# MC_amp.net
KiCad netlist of a schematic drawn in EAGLE
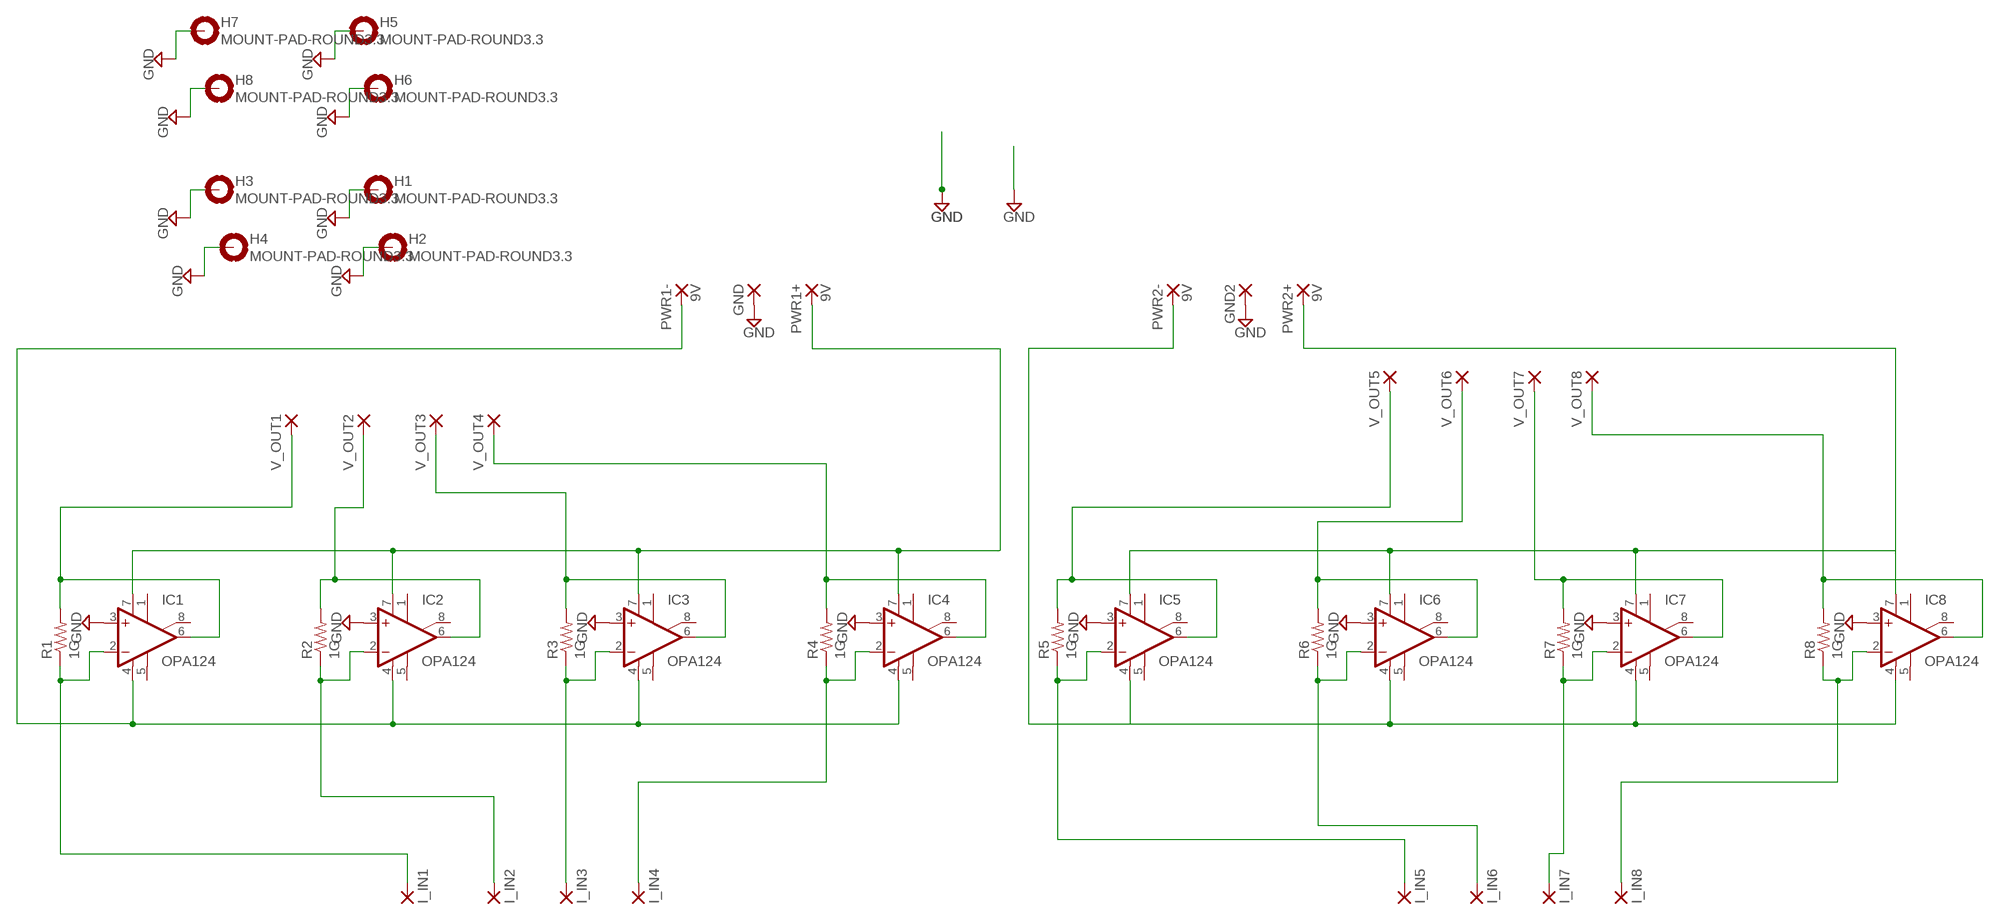
[diagram p0: schematic, sheet 1]

(export (version "E")
  (design (tool "Eeschema 10.0.6"))
  (components
    (comp (ref "GND")
      (value "1,6/0,8")
      (footprint "eagle-import:1,6_0,8")
      (libsource (lib "eagle-import") (part "1,6/0,8"))
    )
    (comp (ref "GND2")
      (value "1,6/0,8")
      (footprint "eagle-import:1,6_0,8")
      (libsource (lib "eagle-import") (part "1,6/0,8"))
    )
    (comp (ref "H1")
      (value "MOUNT-PAD-ROUND3.3")
      (footprint "eagle-import:3,3-PAD")
      (libsource (lib "eagle-import") (part "MOUNT-PAD-ROUND3.3"))
    )
    (comp (ref "H2")
      (value "MOUNT-PAD-ROUND3.3")
      (footprint "eagle-import:3,3-PAD")
      (libsource (lib "eagle-import") (part "MOUNT-PAD-ROUND3.3"))
    )
    (comp (ref "H3")
      (value "MOUNT-PAD-ROUND3.3")
      (footprint "eagle-import:3,3-PAD")
      (libsource (lib "eagle-import") (part "MOUNT-PAD-ROUND3.3"))
    )
    (comp (ref "H4")
      (value "MOUNT-PAD-ROUND3.3")
      (footprint "eagle-import:3,3-PAD")
      (libsource (lib "eagle-import") (part "MOUNT-PAD-ROUND3.3"))
    )
    (comp (ref "H5")
      (value "MOUNT-PAD-ROUND3.3")
      (footprint "eagle-import:3,3-PAD")
      (libsource (lib "eagle-import") (part "MOUNT-PAD-ROUND3.3"))
    )
    (comp (ref "H6")
      (value "MOUNT-PAD-ROUND3.3")
      (footprint "eagle-import:3,3-PAD")
      (libsource (lib "eagle-import") (part "MOUNT-PAD-ROUND3.3"))
    )
    (comp (ref "H7")
      (value "MOUNT-PAD-ROUND3.3")
      (footprint "eagle-import:3,3-PAD")
      (libsource (lib "eagle-import") (part "MOUNT-PAD-ROUND3.3"))
    )
    (comp (ref "H8")
      (value "MOUNT-PAD-ROUND3.3")
      (footprint "eagle-import:3,3-PAD")
      (libsource (lib "eagle-import") (part "MOUNT-PAD-ROUND3.3"))
    )
    (comp (ref "IC1")
      (value "OPA124")
      (footprint "eagle-import:DIL08")
      (libsource (lib "eagle-import") (part "OPA121P"))
    )
    (comp (ref "IC2")
      (value "OPA124")
      (footprint "eagle-import:DIL08")
      (libsource (lib "eagle-import") (part "OPA121P"))
    )
    (comp (ref "IC3")
      (value "OPA124")
      (footprint "eagle-import:DIL08")
      (libsource (lib "eagle-import") (part "OPA121P"))
    )
    (comp (ref "IC4")
      (value "OPA124")
      (footprint "eagle-import:DIL08")
      (libsource (lib "eagle-import") (part "OPA121P"))
    )
    (comp (ref "IC5")
      (value "OPA124")
      (footprint "eagle-import:DIL08")
      (libsource (lib "eagle-import") (part "OPA121P"))
    )
    (comp (ref "IC6")
      (value "OPA124")
      (footprint "eagle-import:DIL08")
      (libsource (lib "eagle-import") (part "OPA121P"))
    )
    (comp (ref "IC7")
      (value "OPA124")
      (footprint "eagle-import:DIL08")
      (libsource (lib "eagle-import") (part "OPA121P"))
    )
    (comp (ref "IC8")
      (value "OPA124")
      (footprint "eagle-import:DIL08")
      (libsource (lib "eagle-import") (part "OPA121P"))
    )
    (comp (ref "I_IN1")
      (value "1,6/0,8")
      (footprint "eagle-import:1,6_0,8")
      (libsource (lib "eagle-import") (part "1,6/0,8"))
    )
    (comp (ref "I_IN2")
      (value "1,6/0,8")
      (footprint "eagle-import:1,6_0,8")
      (libsource (lib "eagle-import") (part "1,6/0,8"))
    )
    (comp (ref "I_IN3")
      (value "1,6/0,8")
      (footprint "eagle-import:1,6_0,8")
      (libsource (lib "eagle-import") (part "1,6/0,8"))
    )
    (comp (ref "I_IN4")
      (value "1,6/0,8")
      (footprint "eagle-import:1,6_0,8")
      (libsource (lib "eagle-import") (part "1,6/0,8"))
    )
    (comp (ref "I_IN5")
      (value "1,6/0,8")
      (footprint "eagle-import:1,6_0,8")
      (libsource (lib "eagle-import") (part "1,6/0,8"))
    )
    (comp (ref "I_IN6")
      (value "1,6/0,8")
      (footprint "eagle-import:1,6_0,8")
      (libsource (lib "eagle-import") (part "1,6/0,8"))
    )
    (comp (ref "I_IN7")
      (value "1,6/0,8")
      (footprint "eagle-import:1,6_0,8")
      (libsource (lib "eagle-import") (part "1,6/0,8"))
    )
    (comp (ref "I_IN8")
      (value "1,6/0,8")
      (footprint "eagle-import:1,6_0,8")
      (libsource (lib "eagle-import") (part "1,6/0,8"))
    )
    (comp (ref "PWR1+")
      (value "9V")
      (footprint "eagle-import:1,6_0,8")
      (libsource (lib "eagle-import") (part "1,6/0,8"))
    )
    (comp (ref "PWR1-")
      (value "9V")
      (footprint "eagle-import:1,6_0,8")
      (libsource (lib "eagle-import") (part "1,6/0,8"))
    )
    (comp (ref "PWR2+")
      (value "9V")
      (footprint "eagle-import:1,6_0,8")
      (libsource (lib "eagle-import") (part "1,6/0,8"))
    )
    (comp (ref "PWR2-")
      (value "9V")
      (footprint "eagle-import:1,6_0,8")
      (libsource (lib "eagle-import") (part "1,6/0,8"))
    )
    (comp (ref "R1")
      (value "1G")
      (footprint "eagle-import:0309_12")
      (libsource (lib "eagle-import") (part "R-US_0309/12"))
    )
    (comp (ref "R2")
      (value "1G")
      (footprint "eagle-import:0309_12")
      (libsource (lib "eagle-import") (part "R-US_0309/12"))
    )
    (comp (ref "R3")
      (value "1G")
      (footprint "eagle-import:0309_12")
      (libsource (lib "eagle-import") (part "R-US_0309/12"))
    )
    (comp (ref "R4")
      (value "1G")
      (footprint "eagle-import:0309_12")
      (libsource (lib "eagle-import") (part "R-US_0309/12"))
    )
    (comp (ref "R5")
      (value "1G")
      (footprint "eagle-import:0309_12")
      (libsource (lib "eagle-import") (part "R-US_0309/12"))
    )
    (comp (ref "R6")
      (value "1G")
      (footprint "eagle-import:0309_12")
      (libsource (lib "eagle-import") (part "R-US_0309/12"))
    )
    (comp (ref "R7")
      (value "1G")
      (footprint "eagle-import:0309_12")
      (libsource (lib "eagle-import") (part "R-US_0309/12"))
    )
    (comp (ref "R8")
      (value "1G")
      (footprint "eagle-import:0309_12")
      (libsource (lib "eagle-import") (part "R-US_0309/12"))
    )
    (comp (ref "V_OUT1")
      (value "1,6/0,8")
      (footprint "eagle-import:1,6_0,8")
      (libsource (lib "eagle-import") (part "1,6/0,8"))
    )
    (comp (ref "V_OUT2")
      (value "1,6/0,8")
      (footprint "eagle-import:1,6_0,8")
      (libsource (lib "eagle-import") (part "1,6/0,8"))
    )
    (comp (ref "V_OUT3")
      (value "1,6/0,8")
      (footprint "eagle-import:1,6_0,8")
      (libsource (lib "eagle-import") (part "1,6/0,8"))
    )
    (comp (ref "V_OUT4")
      (value "1,6/0,8")
      (footprint "eagle-import:1,6_0,8")
      (libsource (lib "eagle-import") (part "1,6/0,8"))
    )
    (comp (ref "V_OUT5")
      (value "1,6/0,8")
      (footprint "eagle-import:1,6_0,8")
      (libsource (lib "eagle-import") (part "1,6/0,8"))
    )
    (comp (ref "V_OUT6")
      (value "1,6/0,8")
      (footprint "eagle-import:1,6_0,8")
      (libsource (lib "eagle-import") (part "1,6/0,8"))
    )
    (comp (ref "V_OUT7")
      (value "1,6/0,8")
      (footprint "eagle-import:1,6_0,8")
      (libsource (lib "eagle-import") (part "1,6/0,8"))
    )
    (comp (ref "V_OUT8")
      (value "1,6/0,8")
      (footprint "eagle-import:1,6_0,8")
      (libsource (lib "eagle-import") (part "1,6/0,8"))
    )
  )
  (nets
    (net (code "1") (name "GND") (class "Default")
      (node (ref "GND") (pin "1") (pinfunction "P_1") (pintype "passive"))
      (node (ref "GND2") (pin "1") (pinfunction "P_1") (pintype "passive"))
      (node (ref "H1") (pin "B3,3") (pinfunction "MOUNT_B3,3") (pintype "passive"))
      (node (ref "H2") (pin "B3,3") (pinfunction "MOUNT_B3,3") (pintype "passive"))
      (node (ref "H3") (pin "B3,3") (pinfunction "MOUNT_B3,3") (pintype "passive"))
      (node (ref "H4") (pin "B3,3") (pinfunction "MOUNT_B3,3") (pintype "passive"))
      (node (ref "H5") (pin "B3,3") (pinfunction "MOUNT_B3,3") (pintype "passive"))
      (node (ref "H6") (pin "B3,3") (pinfunction "MOUNT_B3,3") (pintype "passive"))
      (node (ref "H7") (pin "B3,3") (pinfunction "MOUNT_B3,3") (pintype "passive"))
      (node (ref "H8") (pin "B3,3") (pinfunction "MOUNT_B3,3") (pintype "passive"))
      (node (ref "IC1") (pin "3") (pinfunction "+IN_3") (pintype "input"))
      (node (ref "IC2") (pin "3") (pinfunction "+IN_3") (pintype "input"))
      (node (ref "IC3") (pin "3") (pinfunction "+IN_3") (pintype "input"))
      (node (ref "IC4") (pin "3") (pinfunction "+IN_3") (pintype "input"))
      (node (ref "IC5") (pin "3") (pinfunction "+IN_3") (pintype "input"))
      (node (ref "IC6") (pin "3") (pinfunction "+IN_3") (pintype "input"))
      (node (ref "IC7") (pin "3") (pinfunction "+IN_3") (pintype "input"))
      (node (ref "IC8") (pin "3") (pinfunction "+IN_3") (pintype "input"))
    )
    (net (code "2") (name "Net-(IC1--IN)") (class "Default")
      (node (ref "IC1") (pin "2") (pinfunction "-IN_2") (pintype "input"))
      (node (ref "I_IN1") (pin "1") (pinfunction "P_1") (pintype "passive"))
      (node (ref "R1") (pin "1") (pinfunction "1_1") (pintype "passive"))
    )
    (net (code "3") (name "Net-(IC1-OUT)") (class "Default")
      (node (ref "IC1") (pin "6") (pinfunction "OUT_6") (pintype "output"))
      (node (ref "R1") (pin "2") (pinfunction "2_2") (pintype "passive"))
      (node (ref "V_OUT1") (pin "1") (pinfunction "P_1") (pintype "passive"))
    )
    (net (code "4") (name "Net-(IC1-V+)") (class "Default")
      (node (ref "IC1") (pin "7") (pinfunction "V+_7") (pintype "power_in"))
      (node (ref "IC2") (pin "7") (pinfunction "V+_7") (pintype "power_in"))
      (node (ref "IC3") (pin "7") (pinfunction "V+_7") (pintype "power_in"))
      (node (ref "IC4") (pin "7") (pinfunction "V+_7") (pintype "power_in"))
      (node (ref "PWR1+") (pin "1") (pinfunction "P_1") (pintype "passive"))
    )
    (net (code "5") (name "Net-(IC1-V-)") (class "Default")
      (node (ref "IC1") (pin "4") (pinfunction "V-_4") (pintype "power_in"))
      (node (ref "IC2") (pin "4") (pinfunction "V-_4") (pintype "power_in"))
      (node (ref "IC3") (pin "4") (pinfunction "V-_4") (pintype "power_in"))
      (node (ref "IC4") (pin "4") (pinfunction "V-_4") (pintype "power_in"))
      (node (ref "PWR1-") (pin "1") (pinfunction "P_1") (pintype "passive"))
    )
    (net (code "6") (name "Net-(IC2--IN)") (class "Default")
      (node (ref "IC2") (pin "2") (pinfunction "-IN_2") (pintype "input"))
      (node (ref "I_IN2") (pin "1") (pinfunction "P_1") (pintype "passive"))
      (node (ref "R2") (pin "1") (pinfunction "1_1") (pintype "passive"))
    )
    (net (code "7") (name "Net-(IC2-OUT)") (class "Default")
      (node (ref "IC2") (pin "6") (pinfunction "OUT_6") (pintype "output"))
      (node (ref "R2") (pin "2") (pinfunction "2_2") (pintype "passive"))
      (node (ref "V_OUT2") (pin "1") (pinfunction "P_1") (pintype "passive"))
    )
    (net (code "8") (name "Net-(IC3--IN)") (class "Default")
      (node (ref "IC3") (pin "2") (pinfunction "-IN_2") (pintype "input"))
      (node (ref "I_IN3") (pin "1") (pinfunction "P_1") (pintype "passive"))
      (node (ref "R3") (pin "1") (pinfunction "1_1") (pintype "passive"))
    )
    (net (code "9") (name "Net-(IC3-OUT)") (class "Default")
      (node (ref "IC3") (pin "6") (pinfunction "OUT_6") (pintype "output"))
      (node (ref "R3") (pin "2") (pinfunction "2_2") (pintype "passive"))
      (node (ref "V_OUT3") (pin "1") (pinfunction "P_1") (pintype "passive"))
    )
    (net (code "10") (name "Net-(IC4--IN)") (class "Default")
      (node (ref "IC4") (pin "2") (pinfunction "-IN_2") (pintype "input"))
      (node (ref "I_IN4") (pin "1") (pinfunction "P_1") (pintype "passive"))
      (node (ref "R4") (pin "1") (pinfunction "1_1") (pintype "passive"))
    )
    (net (code "11") (name "Net-(IC4-OUT)") (class "Default")
      (node (ref "IC4") (pin "6") (pinfunction "OUT_6") (pintype "output"))
      (node (ref "R4") (pin "2") (pinfunction "2_2") (pintype "passive"))
      (node (ref "V_OUT4") (pin "1") (pinfunction "P_1") (pintype "passive"))
    )
    (net (code "12") (name "Net-(IC5--IN)") (class "Default")
      (node (ref "IC5") (pin "2") (pinfunction "-IN_2") (pintype "input"))
      (node (ref "I_IN5") (pin "1") (pinfunction "P_1") (pintype "passive"))
      (node (ref "R5") (pin "1") (pinfunction "1_1") (pintype "passive"))
    )
    (net (code "13") (name "Net-(IC5-OUT)") (class "Default")
      (node (ref "IC5") (pin "6") (pinfunction "OUT_6") (pintype "output"))
      (node (ref "R5") (pin "2") (pinfunction "2_2") (pintype "passive"))
      (node (ref "V_OUT5") (pin "1") (pinfunction "P_1") (pintype "passive"))
    )
    (net (code "14") (name "Net-(IC5-V+)") (class "Default")
      (node (ref "IC5") (pin "7") (pinfunction "V+_7") (pintype "power_in"))
      (node (ref "IC6") (pin "7") (pinfunction "V+_7") (pintype "power_in"))
      (node (ref "IC7") (pin "7") (pinfunction "V+_7") (pintype "power_in"))
      (node (ref "IC8") (pin "7") (pinfunction "V+_7") (pintype "power_in"))
      (node (ref "PWR2+") (pin "1") (pinfunction "P_1") (pintype "passive"))
    )
    (net (code "15") (name "Net-(IC5-V-)") (class "Default")
      (node (ref "IC5") (pin "4") (pinfunction "V-_4") (pintype "power_in"))
      (node (ref "IC6") (pin "4") (pinfunction "V-_4") (pintype "power_in"))
      (node (ref "IC7") (pin "4") (pinfunction "V-_4") (pintype "power_in"))
      (node (ref "IC8") (pin "4") (pinfunction "V-_4") (pintype "power_in"))
      (node (ref "PWR2-") (pin "1") (pinfunction "P_1") (pintype "passive"))
    )
    (net (code "16") (name "Net-(IC6--IN)") (class "Default")
      (node (ref "IC6") (pin "2") (pinfunction "-IN_2") (pintype "input"))
      (node (ref "I_IN6") (pin "1") (pinfunction "P_1") (pintype "passive"))
      (node (ref "R6") (pin "1") (pinfunction "1_1") (pintype "passive"))
    )
    (net (code "17") (name "Net-(IC6-OUT)") (class "Default")
      (node (ref "IC6") (pin "6") (pinfunction "OUT_6") (pintype "output"))
      (node (ref "R6") (pin "2") (pinfunction "2_2") (pintype "passive"))
      (node (ref "V_OUT6") (pin "1") (pinfunction "P_1") (pintype "passive"))
    )
    (net (code "18") (name "Net-(IC7--IN)") (class "Default")
      (node (ref "IC7") (pin "2") (pinfunction "-IN_2") (pintype "input"))
      (node (ref "I_IN7") (pin "1") (pinfunction "P_1") (pintype "passive"))
      (node (ref "R7") (pin "1") (pinfunction "1_1") (pintype "passive"))
    )
    (net (code "19") (name "Net-(IC7-OUT)") (class "Default")
      (node (ref "IC7") (pin "6") (pinfunction "OUT_6") (pintype "output"))
      (node (ref "R7") (pin "2") (pinfunction "2_2") (pintype "passive"))
      (node (ref "V_OUT7") (pin "1") (pinfunction "P_1") (pintype "passive"))
    )
    (net (code "20") (name "Net-(IC8--IN)") (class "Default")
      (node (ref "IC8") (pin "2") (pinfunction "-IN_2") (pintype "input"))
      (node (ref "I_IN8") (pin "1") (pinfunction "P_1") (pintype "passive"))
      (node (ref "R8") (pin "1") (pinfunction "1_1") (pintype "passive"))
    )
    (net (code "21") (name "Net-(IC8-OUT)") (class "Default")
      (node (ref "IC8") (pin "6") (pinfunction "OUT_6") (pintype "output"))
      (node (ref "R8") (pin "2") (pinfunction "2_2") (pintype "passive"))
      (node (ref "V_OUT8") (pin "1") (pinfunction "P_1") (pintype "passive"))
    )
    (net (code "22") (name "unconnected-(IC1-ON1-Pad1)") (class "Default")
      (node (ref "IC1") (pin "1") (pinfunction "ON1_1") (pintype "passive"))
    )
    (net (code "23") (name "unconnected-(IC1-ON2-Pad8)") (class "Default")
      (node (ref "IC1") (pin "8") (pinfunction "ON2_8") (pintype "passive"))
    )
    (net (code "24") (name "unconnected-(IC1-OPT-Pad5)") (class "Default")
      (node (ref "IC1") (pin "5") (pinfunction "OPT_5") (pintype "passive"))
    )
    (net (code "25") (name "unconnected-(IC2-ON1-Pad1)") (class "Default")
      (node (ref "IC2") (pin "1") (pinfunction "ON1_1") (pintype "passive"))
    )
    (net (code "26") (name "unconnected-(IC2-ON2-Pad8)") (class "Default")
      (node (ref "IC2") (pin "8") (pinfunction "ON2_8") (pintype "passive"))
    )
    (net (code "27") (name "unconnected-(IC2-OPT-Pad5)") (class "Default")
      (node (ref "IC2") (pin "5") (pinfunction "OPT_5") (pintype "passive"))
    )
    (net (code "28") (name "unconnected-(IC3-ON1-Pad1)") (class "Default")
      (node (ref "IC3") (pin "1") (pinfunction "ON1_1") (pintype "passive"))
    )
    (net (code "29") (name "unconnected-(IC3-ON2-Pad8)") (class "Default")
      (node (ref "IC3") (pin "8") (pinfunction "ON2_8") (pintype "passive"))
    )
    (net (code "30") (name "unconnected-(IC3-OPT-Pad5)") (class "Default")
      (node (ref "IC3") (pin "5") (pinfunction "OPT_5") (pintype "passive"))
    )
    (net (code "31") (name "unconnected-(IC4-ON1-Pad1)") (class "Default")
      (node (ref "IC4") (pin "1") (pinfunction "ON1_1") (pintype "passive"))
    )
    (net (code "32") (name "unconnected-(IC4-ON2-Pad8)") (class "Default")
      (node (ref "IC4") (pin "8") (pinfunction "ON2_8") (pintype "passive"))
    )
    (net (code "33") (name "unconnected-(IC4-OPT-Pad5)") (class "Default")
      (node (ref "IC4") (pin "5") (pinfunction "OPT_5") (pintype "passive"))
    )
    (net (code "34") (name "unconnected-(IC5-ON1-Pad1)") (class "Default")
      (node (ref "IC5") (pin "1") (pinfunction "ON1_1") (pintype "passive"))
    )
    (net (code "35") (name "unconnected-(IC5-ON2-Pad8)") (class "Default")
      (node (ref "IC5") (pin "8") (pinfunction "ON2_8") (pintype "passive"))
    )
    (net (code "36") (name "unconnected-(IC5-OPT-Pad5)") (class "Default")
      (node (ref "IC5") (pin "5") (pinfunction "OPT_5") (pintype "passive"))
    )
    (net (code "37") (name "unconnected-(IC6-ON1-Pad1)") (class "Default")
      (node (ref "IC6") (pin "1") (pinfunction "ON1_1") (pintype "passive"))
    )
    (net (code "38") (name "unconnected-(IC6-ON2-Pad8)") (class "Default")
      (node (ref "IC6") (pin "8") (pinfunction "ON2_8") (pintype "passive"))
    )
    (net (code "39") (name "unconnected-(IC6-OPT-Pad5)") (class "Default")
      (node (ref "IC6") (pin "5") (pinfunction "OPT_5") (pintype "passive"))
    )
    (net (code "40") (name "unconnected-(IC7-ON1-Pad1)") (class "Default")
      (node (ref "IC7") (pin "1") (pinfunction "ON1_1") (pintype "passive"))
    )
    (net (code "41") (name "unconnected-(IC7-ON2-Pad8)") (class "Default")
      (node (ref "IC7") (pin "8") (pinfunction "ON2_8") (pintype "passive"))
    )
    (net (code "42") (name "unconnected-(IC7-OPT-Pad5)") (class "Default")
      (node (ref "IC7") (pin "5") (pinfunction "OPT_5") (pintype "passive"))
    )
    (net (code "43") (name "unconnected-(IC8-ON1-Pad1)") (class "Default")
      (node (ref "IC8") (pin "1") (pinfunction "ON1_1") (pintype "passive"))
    )
    (net (code "44") (name "unconnected-(IC8-ON2-Pad8)") (class "Default")
      (node (ref "IC8") (pin "8") (pinfunction "ON2_8") (pintype "passive"))
    )
    (net (code "45") (name "unconnected-(IC8-OPT-Pad5)") (class "Default")
      (node (ref "IC8") (pin "5") (pinfunction "OPT_5") (pintype "passive"))
    )
  )
)
